# LNA.net
KiCad netlist of a schematic drawn in Altium Designer
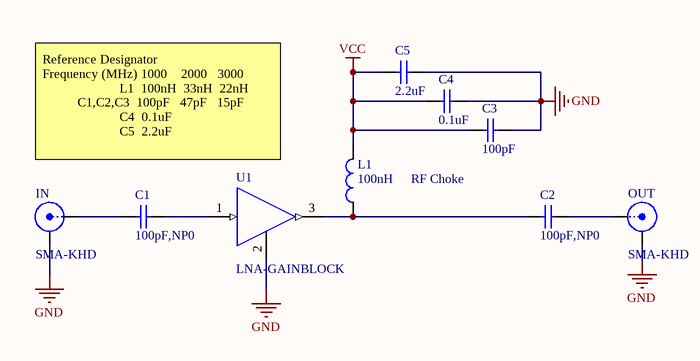
[diagram p0: LNA.SchDoc]

(export (version "E")
  (design (tool "Eeschema 10.0.6"))
  (components
    (comp (ref "C1")
      (value "100pF,NP0")
      (footprint "0603_C")
      (description "Capacitor")
      (fields (field (name "PUBLISHER") "Altium Limited"))
      (libsource (lib "My Footprint") (part "CAP"))
    )
    (comp (ref "C2")
      (value "100pF,NP0")
      (footprint "0603_C")
      (description "Capacitor")
      (fields (field (name "PUBLISHER") "Altium Limited"))
      (libsource (lib "My Footprint") (part "CAP"))
    )
    (comp (ref "C3")
      (value "100pF")
      (footprint "0603_C")
      (description "Capacitor")
      (fields (field (name "PUBLISHER") "Altium Limited"))
      (libsource (lib "My Footprint") (part "CAP"))
    )
    (comp (ref "C4")
      (value "0.1uF")
      (footprint "0603_C")
      (description "Capacitor")
      (fields (field (name "PUBLISHER") "Altium Limited"))
      (libsource (lib "My Footprint") (part "CAP"))
    )
    (comp (ref "C5")
      (value "2.2uF")
      (footprint "0603_C")
      (description "Capacitor")
      (fields (field (name "PUBLISHER") "Altium Limited"))
      (libsource (lib "My Footprint") (part "CAP"))
    )
    (comp (ref "IN") (value "SMA-KHD") (footprint "SMA-2") (libsource (lib "My Footprint") (part "SMA_KHD")))
    (comp (ref "L1")
      (value "100nH")
      (footprint "0603")
      (libsource (lib "My Footprint") (part "L_Inductance"))
    )
    (comp (ref "OUT") (value "SMA-KHD") (footprint "SMA-2") (libsource (lib "My Footprint") (part "SMA_KHD")))
    (comp (ref "U1")
      (value "LNA-GAINBLOCK")
      (footprint "SOT-89")
      (libsource (lib "My Footprint") (part "LNA"))
    )
  )
  (nets
    (net (code "1") (name "GND") (class "Default")
      (node (ref "C3") (pin "2") (pinfunction "2_2") (pintype "passive"))
      (node (ref "C4") (pin "2") (pinfunction "2_2") (pintype "passive"))
      (node (ref "C5") (pin "2") (pinfunction "2_2") (pintype "passive"))
      (node (ref "IN") (pin "1") (pinfunction "Y_1") (pintype "passive"))
      (node (ref "OUT") (pin "1") (pinfunction "Y_1") (pintype "passive"))
      (node (ref "U1") (pin "2") (pinfunction "V-_2") (pintype "power_in"))
    )
    (net (code "2") (name "Net-(IN-X)") (class "Default")
      (node (ref "C1") (pin "1") (pinfunction "1_1") (pintype "passive"))
      (node (ref "IN") (pin "2") (pinfunction "X_2") (pintype "passive"))
    )
    (net (code "3") (name "Net-(OUT-X)") (class "Default")
      (node (ref "C2") (pin "1") (pinfunction "1_1") (pintype "passive"))
      (node (ref "OUT") (pin "2") (pinfunction "X_2") (pintype "passive"))
    )
    (net (code "4") (name "Net-(U1-IN+)") (class "Default")
      (node (ref "C1") (pin "2") (pinfunction "2_2") (pintype "passive"))
      (node (ref "U1") (pin "1") (pinfunction "IN+_1") (pintype "input"))
    )
    (net (code "5") (name "Net-(U1-OUT)") (class "Default")
      (node (ref "C2") (pin "2") (pinfunction "2_2") (pintype "passive"))
      (node (ref "L1") (pin "1") (pinfunction "1_1") (pintype "passive"))
      (node (ref "U1") (pin "3") (pinfunction "OUT_3") (pintype "output"))
    )
    (net (code "6") (name "VCC") (class "Default")
      (node (ref "C3") (pin "1") (pinfunction "1_1") (pintype "passive"))
      (node (ref "C4") (pin "1") (pinfunction "1_1") (pintype "passive"))
      (node (ref "C5") (pin "1") (pinfunction "1_1") (pintype "passive"))
      (node (ref "L1") (pin "2") (pinfunction "2_2") (pintype "passive"))
    )
  )
)
